# Buzzer.net
KiCad netlist of a schematic drawn in Altium Designer
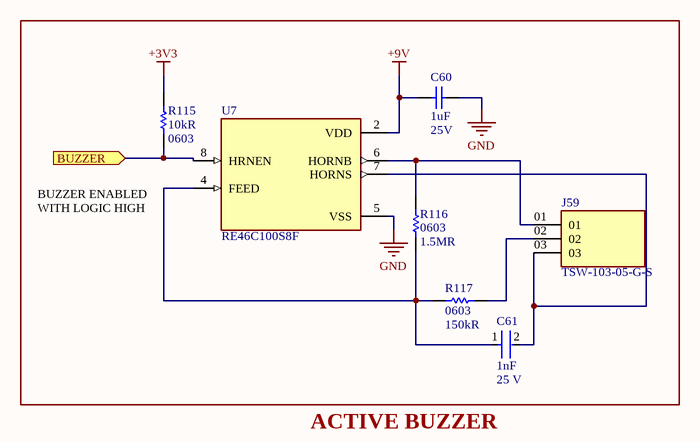
[diagram p0: Buzzer.SchDoc]

(export (version "E")
  (design (tool "Eeschema 10.0.6"))
  (components
    (comp (ref "C60")
      (value "C0603C105K3PAC7867")
      (footprint "CAPC1608X90X35LL15T15")
      (fields
        (field (name "MANUFACTURER") "Kemet")
        (field (name "MANUFACTURER PART NUMBER") "C0603C105K3PACTU")
        (field (name "CAPACITANCE") "1uF")
        (field (name "TOLERANCE") "10%")
        (field (name "VOLTAGE RATING (DC)") "25V")
      )
      (libsource (lib "Altium Content Vault") (part "CAP"))
    )
    (comp (ref "C61")
      (value "C0603C102J3GACTU")
      (footprint "FP-C0603C-CF-MFG")
      (description "CAP CER 1000PF 25V 5% NP0 0603")
      (fields
        (field (name "OCTOPART") "https://octopart.com/c0603c102j3gactu-kemet-8375722")
        (field (name "CAPACITANCE") "1nF")
        (field (name "TOLERANCE") "0.05")
        (field (name "VOLTAGE RATING") "25 V")
      )
      (libsource (lib "Altium Content Vault") (part "b4654b650e69147ec39a6b967a45e02"))
    )
    (comp (ref "J59")
      (value "TSW-103-05-G-S")
      (footprint "TSW-103-05-G-S:SAMTEC_TSW-103-05-G-S")
      (fields (field (name "MF") "{'manufacturer': u'Samtec Inc.'}"))
      (libsource (lib "*") (part "TSW-103-05-G-S"))
    )
    (comp (ref "R115")
      (value "ERJ3EKF1002V")
      (footprint "RESC1609X55X30LL15T15")
      (description "Chip Resistor, 10 KOhm, +/- 1%, 0.1 W, -55 to 155 degC, 0603 (1608 Metric), RoHS, Tape and Reel")
      (fields
        (field (name "RESISTANCE") "10kR")
        (field (name "CASE CODE (IMPERIAL)") "0603")
        (field (name "TOLERANCE") "1%")
        (field (name "MANUFACTURER") "Panasonic")
      )
      (libsource (lib "Altium Content Vault") (part "RES-2"))
    )
    (comp (ref "R116")
      (value "ERJ-3GEYJ155V")
      (footprint "RESC1608X55X30ML15T15")
      (fields
        (field (name "MANUFACTURER") "Panasonic")
        (field (name "CASE CODE (IMPERIAL)") "0603")
        (field (name "RESISTANCE") "1.5MR")
        (field (name "TOLERANCE") "5%")
      )
      (libsource (lib "Altium Content Vault") (part "RES"))
    )
    (comp (ref "R117")
      (value "ERJ-3EKF1503V")
      (footprint "RESC1608X55X30NL15T15")
      (fields
        (field (name "MANUFACTURER") "Panasonic")
        (field (name "CASE CODE (IMPERIAL)") "0603")
        (field (name "RESISTANCE") "150kR")
        (field (name "TOLERANCE") "1%")
      )
      (libsource (lib "Altium Content Vault") (part "RES"))
    )
    (comp (ref "U7")
      (value "RE46C100S8F")
      (footprint "RE46C100S8F:SOIC127P600X175-8N")
      (fields (field (name "MF") "{'manufacturer': u'Microchip Technology'}"))
      (libsource (lib "*") (part "RE46C100S8F"))
    )
  )
  (nets
    (net (code "1") (name "+3V3") (class "Default")
      (node (ref "R115") (pin "2") (pinfunction "2_2") (pintype "passive"))
    )
    (net (code "2") (name "+9V") (class "Default")
      (node (ref "C60") (pin "2") (pinfunction "2_2") (pintype "passive"))
      (node (ref "U7") (pin "2") (pinfunction "VDD_2") (pintype "power_in"))
    )
    (net (code "3") (name "/BUZZER") (class "Default")
      (node (ref "R115") (pin "1") (pinfunction "1_1") (pintype "passive"))
      (node (ref "U7") (pin "8") (pinfunction "HRNEN_8") (pintype "input"))
    )
    (net (code "4") (name "GND") (class "Default")
      (node (ref "C60") (pin "1") (pinfunction "1_1") (pintype "passive"))
      (node (ref "U7") (pin "5") (pinfunction "VSS_5") (pintype "power_in"))
    )
    (net (code "5") (name "Net-(J59-Pad02)") (class "Default")
      (node (ref "J59") (pin "02") (pinfunction "02_02") (pintype "passive"))
      (node (ref "R117") (pin "2") (pinfunction "2_2") (pintype "passive"))
    )
    (net (code "6") (name "Net-(U7-FEED)") (class "Default")
      (node (ref "C61") (pin "1") (pinfunction "1_1") (pintype "passive"))
      (node (ref "R116") (pin "1") (pinfunction "1_1") (pintype "passive"))
      (node (ref "R117") (pin "1") (pinfunction "1_1") (pintype "passive"))
      (node (ref "U7") (pin "4") (pinfunction "FEED_4") (pintype "input"))
    )
    (net (code "7") (name "Net-(U7-HORNB)") (class "Default")
      (node (ref "J59") (pin "01") (pinfunction "01_01") (pintype "passive"))
      (node (ref "R116") (pin "2") (pinfunction "2_2") (pintype "passive"))
      (node (ref "U7") (pin "6") (pinfunction "HORNB_6") (pintype "output"))
    )
    (net (code "8") (name "Net-(U7-HORNS)") (class "Default")
      (node (ref "C61") (pin "2") (pinfunction "2_2") (pintype "passive"))
      (node (ref "J59") (pin "03") (pinfunction "03_03") (pintype "passive"))
      (node (ref "U7") (pin "7") (pinfunction "HORNS_7") (pintype "output"))
    )
  )
)
